# untitled2.net
KiCad netlist of a schematic drawn in EAGLE
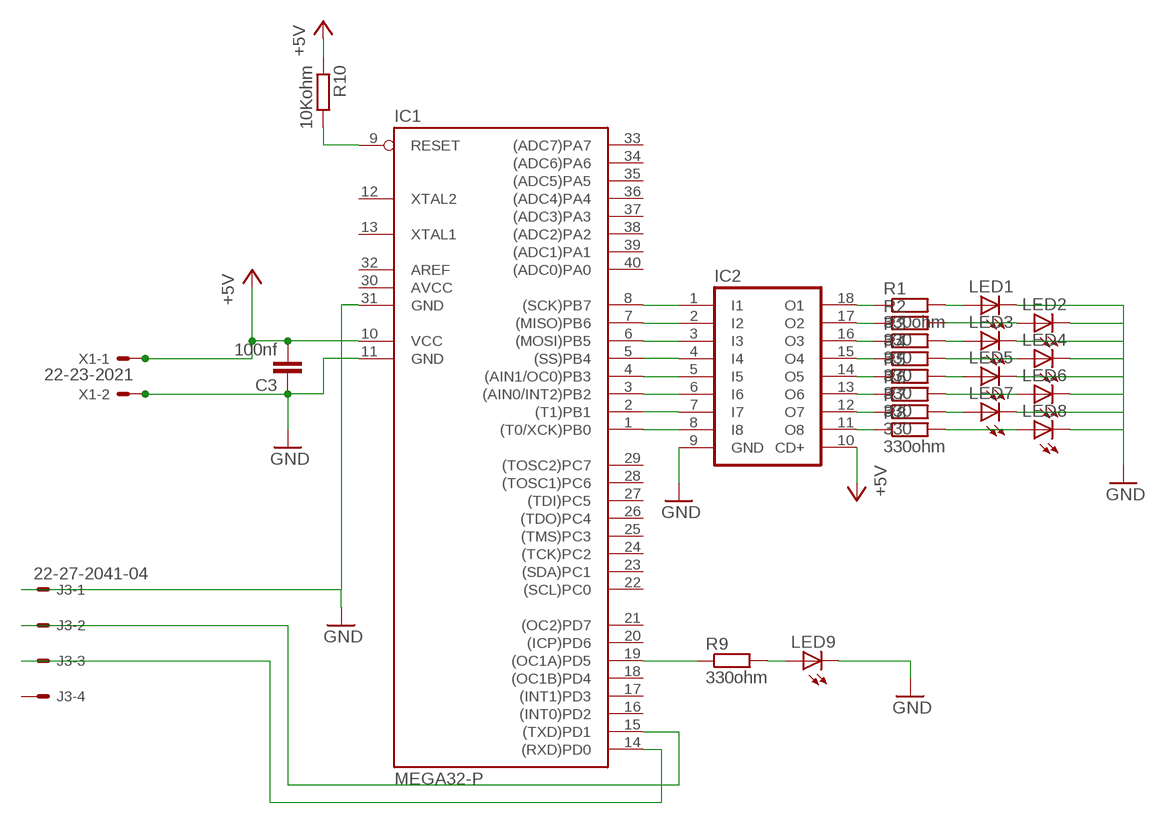
[diagram p0: schematic, sheet 1]

(export (version "E")
  (design (tool "Eeschema 10.0.6"))
  (components
    (comp (ref "C3")
      (value "100nf")
      (footprint "eagle-import:C050-025X075")
      (libsource (lib "eagle-import") (part "C-EU050-025X075"))
    )
    (comp (ref "IC1")
      (value "MEGA32-P")
      (footprint "eagle-import:DIL40")
      (fields (field (name "MPN") "ATMEGA32-16PU"))
      (libsource (lib "eagle-import") (part "MEGA32-P"))
    )
    (comp (ref "IC2")
      (value "ULN2803A")
      (footprint "eagle-import:DIL18")
      (libsource (lib "eagle-import") (part "ULN2803A"))
    )
    (comp (ref "J3")
      (value "22-27-2041-04")
      (footprint "eagle-import:6410-04")
      (libsource (lib "eagle-import") (part "22-?-0427-2041"))
    )
    (comp (ref "LED1")
      (value "LEDIRL80A")
      (footprint "eagle-import:IRL80A")
      (libsource (lib "eagle-import") (part "LEDIRL80A"))
    )
    (comp (ref "LED2")
      (value "LEDIRL80A")
      (footprint "eagle-import:IRL80A")
      (libsource (lib "eagle-import") (part "LEDIRL80A"))
    )
    (comp (ref "LED3")
      (value "LEDIRL80A")
      (footprint "eagle-import:IRL80A")
      (libsource (lib "eagle-import") (part "LEDIRL80A"))
    )
    (comp (ref "LED4")
      (value "LEDIRL80A")
      (footprint "eagle-import:IRL80A")
      (libsource (lib "eagle-import") (part "LEDIRL80A"))
    )
    (comp (ref "LED5")
      (value "LEDIRL80A")
      (footprint "eagle-import:IRL80A")
      (libsource (lib "eagle-import") (part "LEDIRL80A"))
    )
    (comp (ref "LED6")
      (value "LEDIRL80A")
      (footprint "eagle-import:IRL80A")
      (libsource (lib "eagle-import") (part "LEDIRL80A"))
    )
    (comp (ref "LED7")
      (value "LEDIRL80A")
      (footprint "eagle-import:IRL80A")
      (libsource (lib "eagle-import") (part "LEDIRL80A"))
    )
    (comp (ref "LED8")
      (value "LEDIRL80A")
      (footprint "eagle-import:IRL80A")
      (libsource (lib "eagle-import") (part "LEDIRL80A"))
    )
    (comp (ref "LED9")
      (value "LEDIRL80A")
      (footprint "eagle-import:IRL80A")
      (libsource (lib "eagle-import") (part "LEDIRL80A"))
    )
    (comp (ref "R1")
      (value "330ohm")
      (footprint "eagle-import:0207_10")
      (libsource (lib "eagle-import") (part "R-EU_0207/10"))
    )
    (comp (ref "R2")
      (value "330")
      (footprint "eagle-import:0207_10")
      (libsource (lib "eagle-import") (part "R-EU_0207/10"))
    )
    (comp (ref "R3")
      (value "330")
      (footprint "eagle-import:0207_10")
      (libsource (lib "eagle-import") (part "R-EU_0207/10"))
    )
    (comp (ref "R4")
      (value "330")
      (footprint "eagle-import:0207_10")
      (libsource (lib "eagle-import") (part "R-EU_0207/10"))
    )
    (comp (ref "R5")
      (value "330")
      (footprint "eagle-import:0207_10")
      (libsource (lib "eagle-import") (part "R-EU_0207/10"))
    )
    (comp (ref "R6")
      (value "330")
      (footprint "eagle-import:0207_10")
      (libsource (lib "eagle-import") (part "R-EU_0207/10"))
    )
    (comp (ref "R7")
      (value "330")
      (footprint "eagle-import:0207_10")
      (libsource (lib "eagle-import") (part "R-EU_0207/10"))
    )
    (comp (ref "R8")
      (value "330ohm")
      (footprint "eagle-import:0207_10")
      (libsource (lib "eagle-import") (part "R-EU_0207/10"))
    )
    (comp (ref "R9")
      (value "330ohm")
      (footprint "eagle-import:0207_10")
      (libsource (lib "eagle-import") (part "R-EU_0207/10"))
    )
    (comp (ref "R10")
      (value "10Kohm")
      (footprint "eagle-import:0207_10")
      (libsource (lib "eagle-import") (part "R-EU_0207/10"))
    )
    (comp (ref "X1")
      (value "22-23-2021")
      (footprint "eagle-import:22-23-2021")
      (fields (field (name "MF") "MOLEX"))
      (libsource (lib "eagle-import") (part "22-23-2021"))
    )
  )
  (nets
    (net (code "1") (name "+5V") (class "Default")
      (node (ref "C3") (pin "2") (pinfunction "2_2") (pintype "passive"))
      (node (ref "IC1") (pin "10") (pinfunction "VCC_10") (pintype "power_in"))
      (node (ref "IC2") (pin "10") (pinfunction "CD+_10") (pintype "passive"))
      (node (ref "R10") (pin "1") (pinfunction "1_1") (pintype "passive"))
      (node (ref "X1") (pin "1") (pinfunction "S_1") (pintype "passive"))
    )
    (net (code "2") (name "/AVCC") (class "Default")
      (node (ref "IC1") (pin "30") (pinfunction "AVCC_30") (pintype "power_in"))
    )
    (net (code "3") (name "GND") (class "Default")
      (node (ref "C3") (pin "1") (pinfunction "1_1") (pintype "passive"))
      (node (ref "IC1") (pin "11") (pinfunction "GND_11") (pintype "power_in"))
      (node (ref "IC1") (pin "31") (pinfunction "GND_31") (pintype "power_in"))
      (node (ref "IC2") (pin "9") (pinfunction "GND_9") (pintype "power_in"))
      (node (ref "J3") (pin "1") (pinfunction "S_1") (pintype "passive"))
      (node (ref "LED1") (pin "K") (pinfunction "C_K") (pintype "passive"))
      (node (ref "LED2") (pin "K") (pinfunction "C_K") (pintype "passive"))
      (node (ref "LED3") (pin "K") (pinfunction "C_K") (pintype "passive"))
      (node (ref "LED4") (pin "K") (pinfunction "C_K") (pintype "passive"))
      (node (ref "LED5") (pin "K") (pinfunction "C_K") (pintype "passive"))
      (node (ref "LED6") (pin "K") (pinfunction "C_K") (pintype "passive"))
      (node (ref "LED7") (pin "K") (pinfunction "C_K") (pintype "passive"))
      (node (ref "LED8") (pin "K") (pinfunction "C_K") (pintype "passive"))
      (node (ref "LED9") (pin "K") (pinfunction "C_K") (pintype "passive"))
      (node (ref "X1") (pin "2") (pinfunction "S_2") (pintype "passive"))
    )
    (net (code "4") (name "Net-(IC1-(AIN0{slash}INT2)PB2)") (class "Default")
      (node (ref "IC1") (pin "3") (pinfunction "(AIN0/INT2)PB2_3") (pintype "bidirectional"))
      (node (ref "IC2") (pin "6") (pinfunction "I6_6") (pintype "input"))
    )
    (net (code "5") (name "Net-(IC1-(AIN1{slash}OC0)PB3)") (class "Default")
      (node (ref "IC1") (pin "4") (pinfunction "(AIN1/OC0)PB3_4") (pintype "bidirectional"))
      (node (ref "IC2") (pin "5") (pinfunction "I5_5") (pintype "input"))
    )
    (net (code "6") (name "Net-(IC1-(MISO)PB6)") (class "Default")
      (node (ref "IC1") (pin "7") (pinfunction "(MISO)PB6_7") (pintype "bidirectional"))
      (node (ref "IC2") (pin "2") (pinfunction "I2_2") (pintype "input"))
    )
    (net (code "7") (name "Net-(IC1-(MOSI)PB5)") (class "Default")
      (node (ref "IC1") (pin "6") (pinfunction "(MOSI)PB5_6") (pintype "bidirectional"))
      (node (ref "IC2") (pin "3") (pinfunction "I3_3") (pintype "input"))
    )
    (net (code "8") (name "Net-(IC1-(OC1A)PD5)") (class "Default")
      (node (ref "IC1") (pin "19") (pinfunction "(OC1A)PD5_19") (pintype "bidirectional"))
      (node (ref "R9") (pin "1") (pinfunction "1_1") (pintype "passive"))
    )
    (net (code "9") (name "Net-(IC1-(RXD)PD0)") (class "Default")
      (node (ref "IC1") (pin "14") (pinfunction "(RXD)PD0_14") (pintype "bidirectional"))
      (node (ref "J3") (pin "3") (pinfunction "S_3") (pintype "passive"))
    )
    (net (code "10") (name "Net-(IC1-(SCK)PB7)") (class "Default")
      (node (ref "IC1") (pin "8") (pinfunction "(SCK)PB7_8") (pintype "bidirectional"))
      (node (ref "IC2") (pin "1") (pinfunction "I1_1") (pintype "input"))
    )
    (net (code "11") (name "Net-(IC1-(SS)PB4)") (class "Default")
      (node (ref "IC1") (pin "5") (pinfunction "(SS)PB4_5") (pintype "bidirectional"))
      (node (ref "IC2") (pin "4") (pinfunction "I4_4") (pintype "input"))
    )
    (net (code "12") (name "Net-(IC1-(T0{slash}XCK)PB0)") (class "Default")
      (node (ref "IC1") (pin "1") (pinfunction "(T0/XCK)PB0_1") (pintype "bidirectional"))
      (node (ref "IC2") (pin "8") (pinfunction "I8_8") (pintype "input"))
    )
    (net (code "13") (name "Net-(IC1-(T1)PB1)") (class "Default")
      (node (ref "IC1") (pin "2") (pinfunction "(T1)PB1_2") (pintype "bidirectional"))
      (node (ref "IC2") (pin "7") (pinfunction "I7_7") (pintype "input"))
    )
    (net (code "14") (name "Net-(IC1-(TXD)PD1)") (class "Default")
      (node (ref "IC1") (pin "15") (pinfunction "(TXD)PD1_15") (pintype "bidirectional"))
      (node (ref "J3") (pin "2") (pinfunction "S_2") (pintype "passive"))
    )
    (net (code "15") (name "Net-(IC1-RESET)") (class "Default")
      (node (ref "IC1") (pin "9") (pinfunction "RESET_9") (pintype "input"))
      (node (ref "R10") (pin "2") (pinfunction "2_2") (pintype "passive"))
    )
    (net (code "16") (name "Net-(IC2-O1)") (class "Default")
      (node (ref "IC2") (pin "18") (pinfunction "O1_18") (pintype "open_collector"))
      (node (ref "R1") (pin "1") (pinfunction "1_1") (pintype "passive"))
    )
    (net (code "17") (name "Net-(IC2-O2)") (class "Default")
      (node (ref "IC2") (pin "17") (pinfunction "O2_17") (pintype "open_collector"))
      (node (ref "R2") (pin "1") (pinfunction "1_1") (pintype "passive"))
    )
    (net (code "18") (name "Net-(IC2-O3)") (class "Default")
      (node (ref "IC2") (pin "16") (pinfunction "O3_16") (pintype "open_collector"))
      (node (ref "R3") (pin "1") (pinfunction "1_1") (pintype "passive"))
    )
    (net (code "19") (name "Net-(IC2-O4)") (class "Default")
      (node (ref "IC2") (pin "15") (pinfunction "O4_15") (pintype "open_collector"))
      (node (ref "R4") (pin "1") (pinfunction "1_1") (pintype "passive"))
    )
    (net (code "20") (name "Net-(IC2-O5)") (class "Default")
      (node (ref "IC2") (pin "14") (pinfunction "O5_14") (pintype "open_collector"))
      (node (ref "R5") (pin "1") (pinfunction "1_1") (pintype "passive"))
    )
    (net (code "21") (name "Net-(IC2-O6)") (class "Default")
      (node (ref "IC2") (pin "13") (pinfunction "O6_13") (pintype "open_collector"))
      (node (ref "R6") (pin "1") (pinfunction "1_1") (pintype "passive"))
    )
    (net (code "22") (name "Net-(IC2-O7)") (class "Default")
      (node (ref "IC2") (pin "12") (pinfunction "O7_12") (pintype "open_collector"))
      (node (ref "R7") (pin "1") (pinfunction "1_1") (pintype "passive"))
    )
    (net (code "23") (name "Net-(IC2-O8)") (class "Default")
      (node (ref "IC2") (pin "11") (pinfunction "O8_11") (pintype "open_collector"))
      (node (ref "R8") (pin "1") (pinfunction "1_1") (pintype "passive"))
    )
    (net (code "24") (name "Net-(LED1-PadA)") (class "Default")
      (node (ref "LED1") (pin "A") (pinfunction "A_A") (pintype "passive"))
      (node (ref "R1") (pin "2") (pinfunction "2_2") (pintype "passive"))
    )
    (net (code "25") (name "Net-(LED2-PadA)") (class "Default")
      (node (ref "LED2") (pin "A") (pinfunction "A_A") (pintype "passive"))
      (node (ref "R2") (pin "2") (pinfunction "2_2") (pintype "passive"))
    )
    (net (code "26") (name "Net-(LED3-PadA)") (class "Default")
      (node (ref "LED3") (pin "A") (pinfunction "A_A") (pintype "passive"))
      (node (ref "R3") (pin "2") (pinfunction "2_2") (pintype "passive"))
    )
    (net (code "27") (name "Net-(LED4-PadA)") (class "Default")
      (node (ref "LED4") (pin "A") (pinfunction "A_A") (pintype "passive"))
      (node (ref "R4") (pin "2") (pinfunction "2_2") (pintype "passive"))
    )
    (net (code "28") (name "Net-(LED5-PadA)") (class "Default")
      (node (ref "LED5") (pin "A") (pinfunction "A_A") (pintype "passive"))
      (node (ref "R5") (pin "2") (pinfunction "2_2") (pintype "passive"))
    )
    (net (code "29") (name "Net-(LED6-PadA)") (class "Default")
      (node (ref "LED6") (pin "A") (pinfunction "A_A") (pintype "passive"))
      (node (ref "R6") (pin "2") (pinfunction "2_2") (pintype "passive"))
    )
    (net (code "30") (name "Net-(LED7-PadA)") (class "Default")
      (node (ref "LED7") (pin "A") (pinfunction "A_A") (pintype "passive"))
      (node (ref "R7") (pin "2") (pinfunction "2_2") (pintype "passive"))
    )
    (net (code "31") (name "Net-(LED8-PadA)") (class "Default")
      (node (ref "LED8") (pin "A") (pinfunction "A_A") (pintype "passive"))
      (node (ref "R8") (pin "2") (pinfunction "2_2") (pintype "passive"))
    )
    (net (code "32") (name "Net-(LED9-PadA)") (class "Default")
      (node (ref "LED9") (pin "A") (pinfunction "A_A") (pintype "passive"))
      (node (ref "R9") (pin "2") (pinfunction "2_2") (pintype "passive"))
    )
    (net (code "33") (name "unconnected-(IC1-(ADC0)PA0-Pad40)") (class "Default")
      (node (ref "IC1") (pin "40") (pinfunction "(ADC0)PA0_40") (pintype "bidirectional"))
    )
    (net (code "34") (name "unconnected-(IC1-(ADC1)PA1-Pad39)") (class "Default")
      (node (ref "IC1") (pin "39") (pinfunction "(ADC1)PA1_39") (pintype "bidirectional"))
    )
    (net (code "35") (name "unconnected-(IC1-(ADC2)PA2-Pad38)") (class "Default")
      (node (ref "IC1") (pin "38") (pinfunction "(ADC2)PA2_38") (pintype "bidirectional"))
    )
    (net (code "36") (name "unconnected-(IC1-(ADC3)PA3-Pad37)") (class "Default")
      (node (ref "IC1") (pin "37") (pinfunction "(ADC3)PA3_37") (pintype "bidirectional"))
    )
    (net (code "37") (name "unconnected-(IC1-(ADC4)PA4-Pad36)") (class "Default")
      (node (ref "IC1") (pin "36") (pinfunction "(ADC4)PA4_36") (pintype "bidirectional"))
    )
    (net (code "38") (name "unconnected-(IC1-(ADC5)PA5-Pad35)") (class "Default")
      (node (ref "IC1") (pin "35") (pinfunction "(ADC5)PA5_35") (pintype "bidirectional"))
    )
    (net (code "39") (name "unconnected-(IC1-(ADC6)PA6-Pad34)") (class "Default")
      (node (ref "IC1") (pin "34") (pinfunction "(ADC6)PA6_34") (pintype "bidirectional"))
    )
    (net (code "40") (name "unconnected-(IC1-(ADC7)PA7-Pad33)") (class "Default")
      (node (ref "IC1") (pin "33") (pinfunction "(ADC7)PA7_33") (pintype "bidirectional"))
    )
    (net (code "41") (name "unconnected-(IC1-(ICP)PD6-Pad20)") (class "Default")
      (node (ref "IC1") (pin "20") (pinfunction "(ICP)PD6_20") (pintype "bidirectional"))
    )
    (net (code "42") (name "unconnected-(IC1-(INT0)PD2-Pad16)") (class "Default")
      (node (ref "IC1") (pin "16") (pinfunction "(INT0)PD2_16") (pintype "bidirectional"))
    )
    (net (code "43") (name "unconnected-(IC1-(INT1)PD3-Pad17)") (class "Default")
      (node (ref "IC1") (pin "17") (pinfunction "(INT1)PD3_17") (pintype "bidirectional"))
    )
    (net (code "44") (name "unconnected-(IC1-(OC1B)PD4-Pad18)") (class "Default")
      (node (ref "IC1") (pin "18") (pinfunction "(OC1B)PD4_18") (pintype "bidirectional"))
    )
    (net (code "45") (name "unconnected-(IC1-(OC2)PD7-Pad21)") (class "Default")
      (node (ref "IC1") (pin "21") (pinfunction "(OC2)PD7_21") (pintype "bidirectional"))
    )
    (net (code "46") (name "unconnected-(IC1-(SCL)PC0-Pad22)") (class "Default")
      (node (ref "IC1") (pin "22") (pinfunction "(SCL)PC0_22") (pintype "bidirectional"))
    )
    (net (code "47") (name "unconnected-(IC1-(SDA)PC1-Pad23)") (class "Default")
      (node (ref "IC1") (pin "23") (pinfunction "(SDA)PC1_23") (pintype "bidirectional"))
    )
    (net (code "48") (name "unconnected-(IC1-(TCK)PC2-Pad24)") (class "Default")
      (node (ref "IC1") (pin "24") (pinfunction "(TCK)PC2_24") (pintype "bidirectional"))
    )
    (net (code "49") (name "unconnected-(IC1-(TDI)PC5-Pad27)") (class "Default")
      (node (ref "IC1") (pin "27") (pinfunction "(TDI)PC5_27") (pintype "bidirectional"))
    )
    (net (code "50") (name "unconnected-(IC1-(TDO)PC4-Pad26)") (class "Default")
      (node (ref "IC1") (pin "26") (pinfunction "(TDO)PC4_26") (pintype "bidirectional"))
    )
    (net (code "51") (name "unconnected-(IC1-(TMS)PC3-Pad25)") (class "Default")
      (node (ref "IC1") (pin "25") (pinfunction "(TMS)PC3_25") (pintype "bidirectional"))
    )
    (net (code "52") (name "unconnected-(IC1-(TOSC1)PC6-Pad28)") (class "Default")
      (node (ref "IC1") (pin "28") (pinfunction "(TOSC1)PC6_28") (pintype "bidirectional"))
    )
    (net (code "53") (name "unconnected-(IC1-(TOSC2)PC7-Pad29)") (class "Default")
      (node (ref "IC1") (pin "29") (pinfunction "(TOSC2)PC7_29") (pintype "bidirectional"))
    )
    (net (code "54") (name "unconnected-(IC1-AREF-Pad32)") (class "Default")
      (node (ref "IC1") (pin "32") (pinfunction "AREF_32") (pintype "passive"))
    )
    (net (code "55") (name "unconnected-(IC1-XTAL1-Pad13)") (class "Default")
      (node (ref "IC1") (pin "13") (pinfunction "XTAL1_13") (pintype "bidirectional"))
    )
    (net (code "56") (name "unconnected-(IC1-XTAL2-Pad12)") (class "Default")
      (node (ref "IC1") (pin "12") (pinfunction "XTAL2_12") (pintype "bidirectional"))
    )
    (net (code "57") (name "unconnected-(J3D-S-Pad4)") (class "Default")
      (node (ref "J3") (pin "4") (pinfunction "S_4") (pintype "passive"))
    )
  )
)
